# twentyfive.net
KiCad netlist of a schematic drawn in Altium Designer
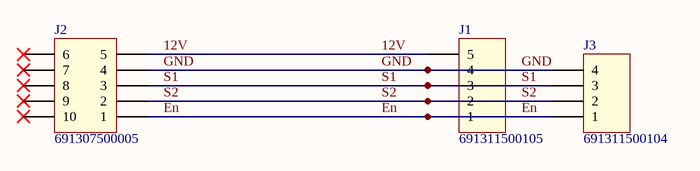
[diagram p0: twentyfive.SchDoc]

(export (version "E")
  (design (tool "Eeschema 10.0.6"))
  (components
    (comp (ref "J1")
      (value "691311500105")
      (footprint "691311500105")
      (description "WR-TBL Serie 311 - 5.08 mm Close Vertical PCB Header, 05p")
      (fields (field (name "PUBLISHER") "Wurth Elektronik"))
      (libsource (lib "ALTIUM-TBL_5_08_3075_REVERSED_GENDER_VERTICAL_PCB_HEADER_69130750000X-rev17a") (part "691311500105"))
    )
    (comp (ref "J2")
      (value "691307500005")
      (footprint "691307500005")
      (description "WR-TBL Serie 3075 - 5.08 mm Reversed Gender Vertical PCB Header, 05p")
      (fields (field (name "PUBLISHER") "Wurth Elektronik"))
      (libsource (lib "ALTIUM-TBL_5_08_3075_REVERSED_GENDER_VERTICAL_PCB_HEADER_69130750000X-rev17a") (part "691307500005"))
    )
    (comp (ref "J3")
      (value "691311500104")
      (footprint "691311500104")
      (description "WR-TBL Serie 311 - 5.08 mm Close Vertical PCB Header, 04p")
      (fields (field (name "PUBLISHER") "Wurth Elektronik"))
      (libsource (lib "ALTIUM-TBL_5_08_3075_REVERSED_GENDER_VERTICAL_PCB_HEADER_69130750000X-rev17a") (part "691311500104"))
    )
  )
  (nets
    (net (code "1") (name "/12V") (class "Default")
      (node (ref "J1") (pin "5") (pinfunction "5_5") (pintype "passive"))
      (node (ref "J2") (pin "5") (pinfunction "5_5") (pintype "passive"))
    )
    (net (code "2") (name "/En") (class "Default")
      (node (ref "J1") (pin "1") (pinfunction "1_1") (pintype "passive"))
      (node (ref "J2") (pin "1") (pinfunction "1_1") (pintype "passive"))
      (node (ref "J3") (pin "1") (pinfunction "1_1") (pintype "passive"))
    )
    (net (code "3") (name "/GND") (class "Default")
      (node (ref "J1") (pin "4") (pinfunction "4_4") (pintype "passive"))
      (node (ref "J2") (pin "4") (pinfunction "4_4") (pintype "passive"))
      (node (ref "J3") (pin "4") (pinfunction "4_4") (pintype "passive"))
    )
    (net (code "4") (name "/S1") (class "Default")
      (node (ref "J1") (pin "3") (pinfunction "3_3") (pintype "passive"))
      (node (ref "J2") (pin "3") (pinfunction "3_3") (pintype "passive"))
      (node (ref "J3") (pin "3") (pinfunction "3_3") (pintype "passive"))
    )
    (net (code "5") (name "/S2") (class "Default")
      (node (ref "J1") (pin "2") (pinfunction "2_2") (pintype "passive"))
      (node (ref "J2") (pin "2") (pinfunction "2_2") (pintype "passive"))
      (node (ref "J3") (pin "2") (pinfunction "2_2") (pintype "passive"))
    )
    (net (code "6") (name "unconnected-(J2-Pad6)") (class "Default")
      (node (ref "J2") (pin "6") (pinfunction "6_6") (pintype "passive+no_connect"))
    )
    (net (code "7") (name "unconnected-(J2-Pad7)") (class "Default")
      (node (ref "J2") (pin "7") (pinfunction "7_7") (pintype "passive+no_connect"))
    )
    (net (code "8") (name "unconnected-(J2-Pad8)") (class "Default")
      (node (ref "J2") (pin "8") (pinfunction "8_8") (pintype "passive+no_connect"))
    )
    (net (code "9") (name "unconnected-(J2-Pad9)") (class "Default")
      (node (ref "J2") (pin "9") (pinfunction "9_9") (pintype "passive+no_connect"))
    )
    (net (code "10") (name "unconnected-(J2-Pad10)") (class "Default")
      (node (ref "J2") (pin "10") (pinfunction "10_10") (pintype "passive+no_connect"))
    )
  )
)
